# 10-RF_WIFI.net
KiCad netlist of a schematic drawn in Altium Designer
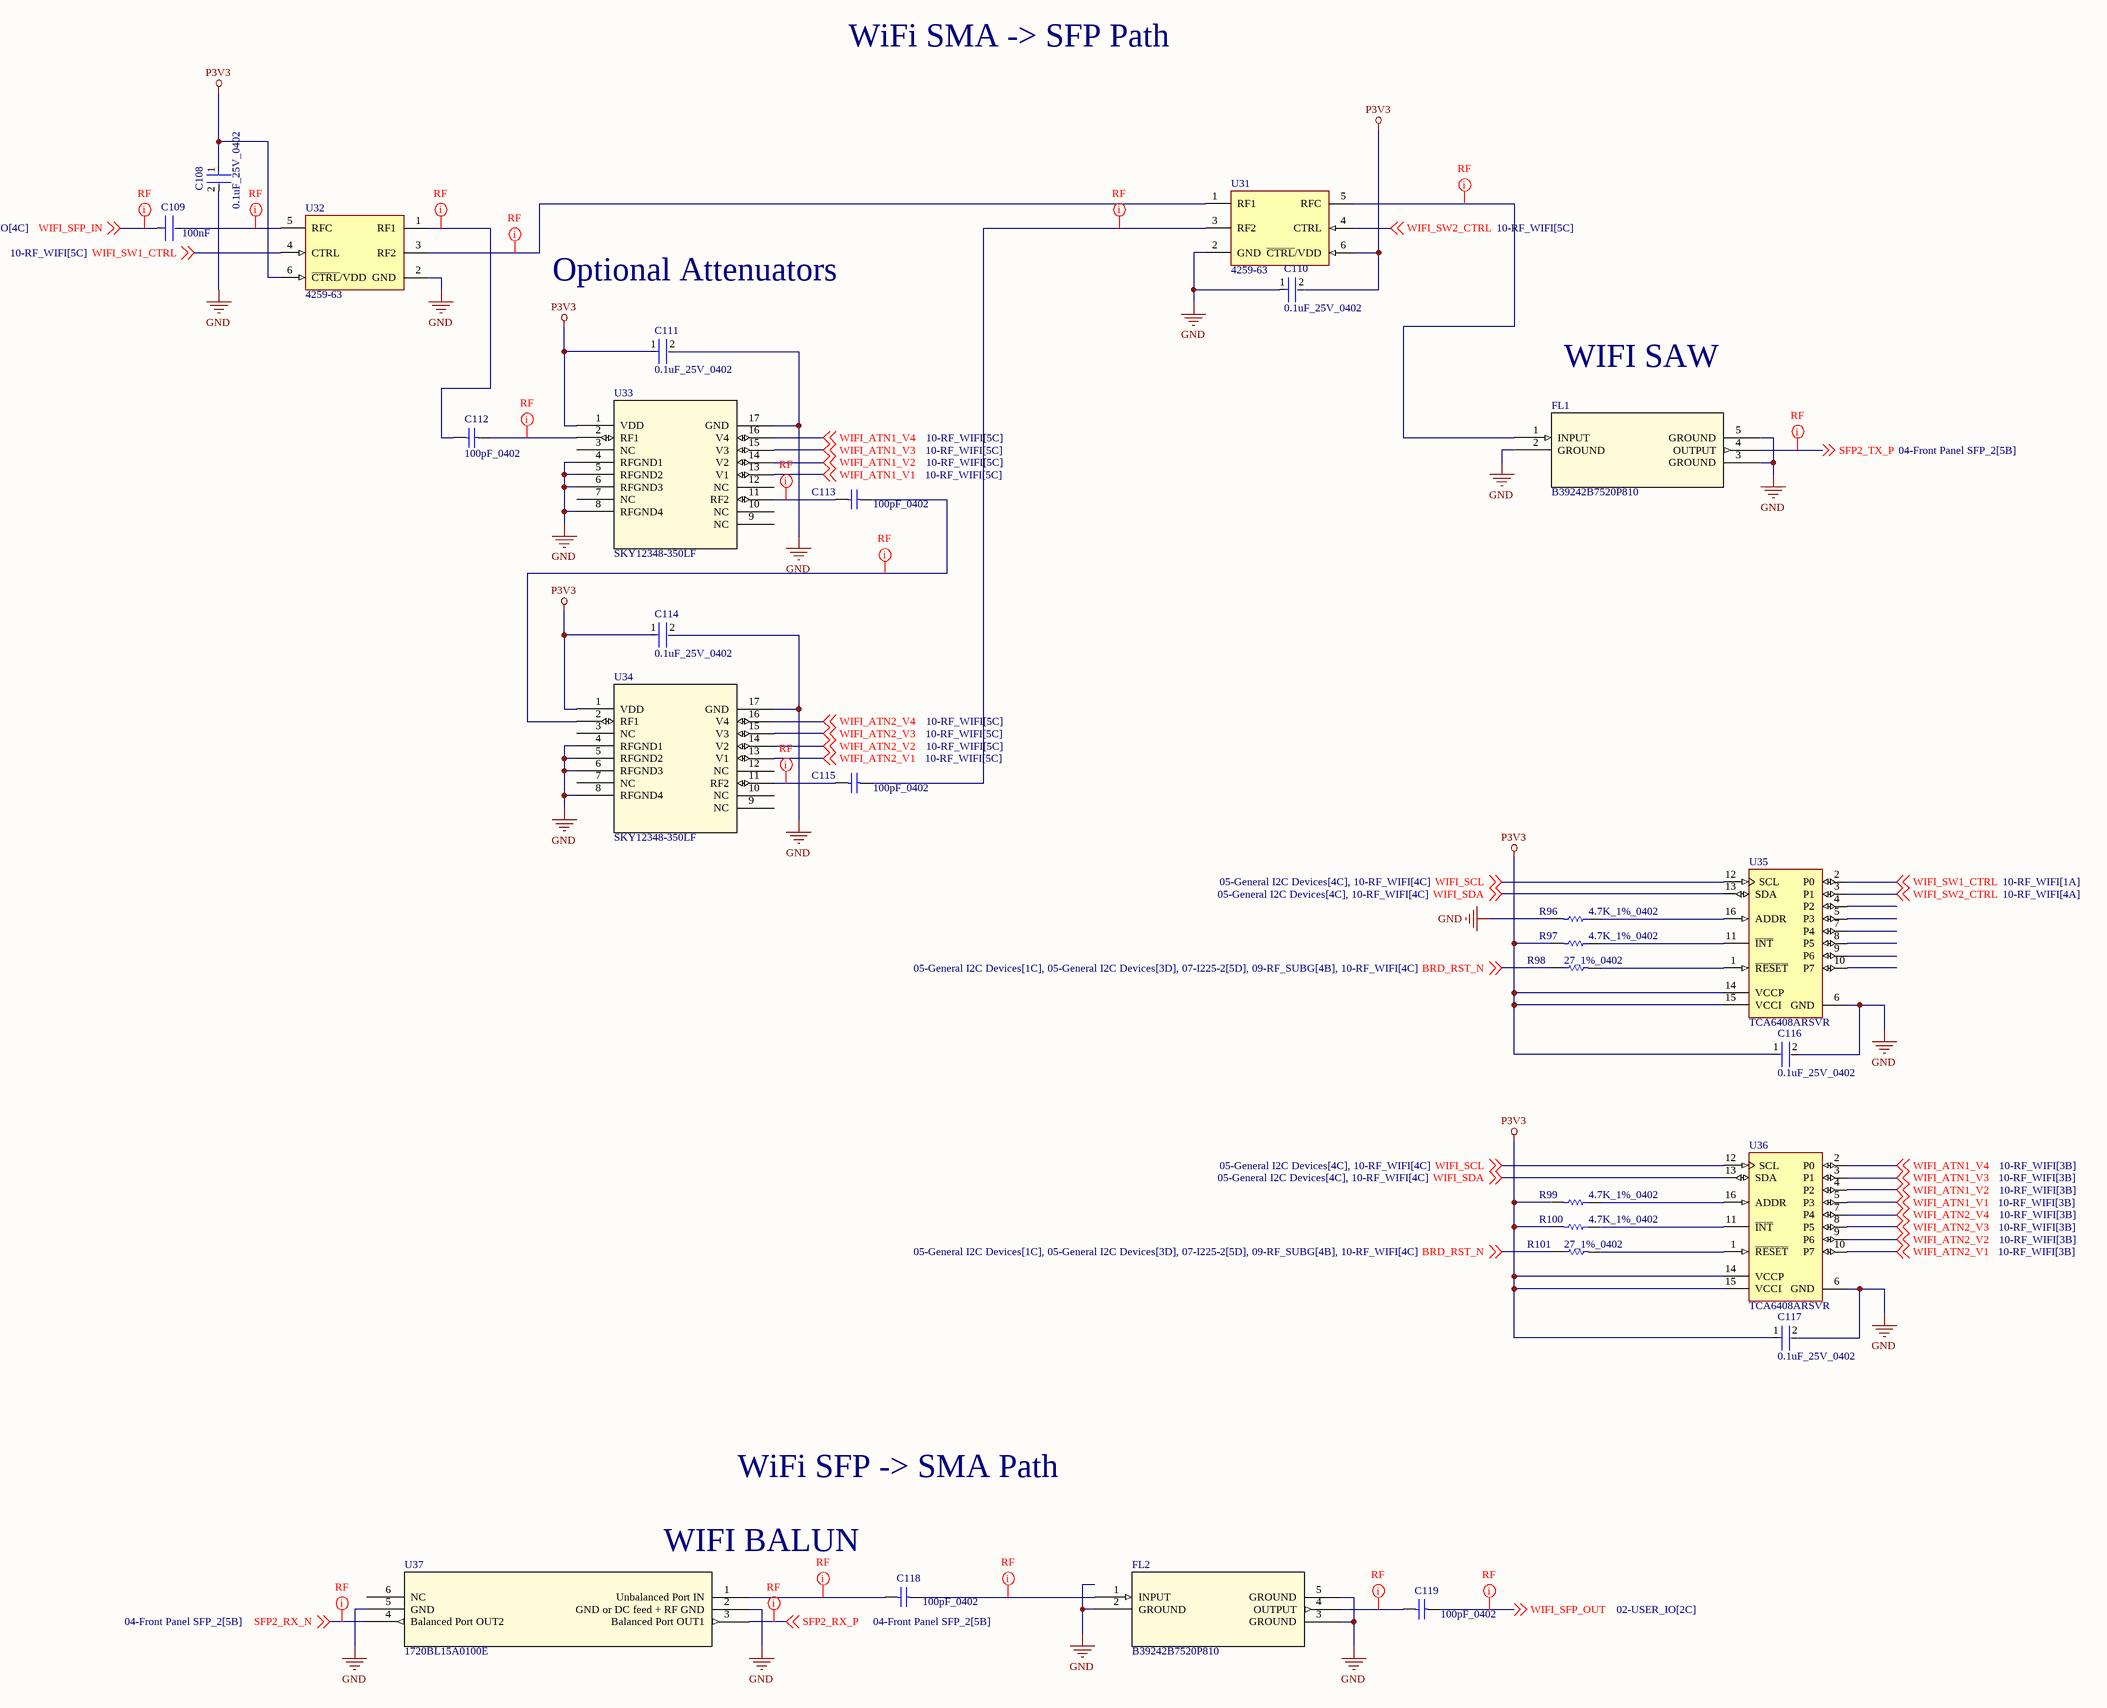
[diagram p0: 10-RF_WIFI.SchDoc]

(export (version "E")
  (design (tool "Eeschema 10.0.6"))
  (components
    (comp (ref "C108")
      (value "0.1uF_25V_0402")
      (footprint "FP-0402-L_1_0_1-W_0_5_0_1-IPC_C")
      (description "General Purpose Ceramic Capacitor, 0402, 100nF, 10%, X7R, 15%, 25V")
      (fields (field (name "VOLTAGE") "25V") (field (name "TOLERANCE") "10%"))
      (libsource (lib "Altium Content Vault") (part "b4654b650e69147ec39a6b967a45e02"))
    )
    (comp (ref "C109")
      (value "100nF")
      (footprint "FP-0402-L_1_0_0_05-W_0_5-IPC_B")
      (description "None")
      (fields (field (name "TOLERANCE") "10%"))
      (libsource (lib "") (part "b4654b650e69147ec39a6b967a45e02_1"))
    )
    (comp (ref "C110")
      (value "0.1uF_25V_0402")
      (footprint "FP-0402-L_1_0_1-W_0_5_0_1-IPC_C")
      (description "General Purpose Ceramic Capacitor, 0402, 100nF, 10%, X7R, 15%, 25V")
      (fields (field (name "VOLTAGE") "25V") (field (name "TOLERANCE") "10%"))
      (libsource (lib "Altium Content Vault") (part "b4654b650e69147ec39a6b967a45e02"))
    )
    (comp (ref "C111")
      (value "0.1uF_25V_0402")
      (footprint "FP-0402-L_1_0_1-W_0_5_0_1-IPC_C")
      (description "General Purpose Ceramic Capacitor, 0402, 100nF, 10%, X7R, 15%, 25V")
      (fields (field (name "VOLTAGE") "25V") (field (name "TOLERANCE") "10%"))
      (libsource (lib "Altium Content Vault") (part "b4654b650e69147ec39a6b967a45e02"))
    )
    (comp (ref "C112")
      (value "100pF_0402")
      (footprint "CAPC1005X55X25ML05T10")
      (fields (field (name "MANUFACTURER") "Murata") (field (name "PART NUMBER") "GRM1555C1H101JA01D"))
      (libsource (lib "Altium Content Vault") (part "CAP"))
    )
    (comp (ref "C113")
      (value "100pF_0402")
      (footprint "CAPC1005X55X25ML05T10")
      (fields (field (name "MANUFACTURER") "Murata") (field (name "PART NUMBER") "GRM1555C1H101JA01D"))
      (libsource (lib "Altium Content Vault") (part "CAP"))
    )
    (comp (ref "C114")
      (value "0.1uF_25V_0402")
      (footprint "FP-0402-L_1_0_1-W_0_5_0_1-IPC_C")
      (description "General Purpose Ceramic Capacitor, 0402, 100nF, 10%, X7R, 15%, 25V")
      (fields (field (name "VOLTAGE") "25V") (field (name "TOLERANCE") "10%"))
      (libsource (lib "Altium Content Vault") (part "b4654b650e69147ec39a6b967a45e02"))
    )
    (comp (ref "C115")
      (value "100pF_0402")
      (footprint "CAPC1005X55X25ML05T10")
      (fields (field (name "MANUFACTURER") "Murata") (field (name "PART NUMBER") "GRM1555C1H101JA01D"))
      (libsource (lib "Altium Content Vault") (part "CAP"))
    )
    (comp (ref "C116")
      (value "0.1uF_25V_0402")
      (footprint "FP-0402-L_1_0_1-W_0_5_0_1-IPC_C")
      (description "General Purpose Ceramic Capacitor, 0402, 100nF, 10%, X7R, 15%, 25V")
      (fields (field (name "VOLTAGE") "25V") (field (name "TOLERANCE") "10%"))
      (libsource (lib "Altium Content Vault") (part "b4654b650e69147ec39a6b967a45e02"))
    )
    (comp (ref "C117")
      (value "0.1uF_25V_0402")
      (footprint "FP-0402-L_1_0_1-W_0_5_0_1-IPC_C")
      (description "General Purpose Ceramic Capacitor, 0402, 100nF, 10%, X7R, 15%, 25V")
      (fields (field (name "VOLTAGE") "25V") (field (name "TOLERANCE") "10%"))
      (libsource (lib "Altium Content Vault") (part "b4654b650e69147ec39a6b967a45e02"))
    )
    (comp (ref "C118")
      (value "100pF_0402")
      (footprint "CAPC1005X55X25ML05T10")
      (fields (field (name "MANUFACTURER") "Murata") (field (name "PART NUMBER") "GRM1555C1H101JA01D"))
      (libsource (lib "Altium Content Vault") (part "CAP"))
    )
    (comp (ref "C119")
      (value "100pF_0402")
      (footprint "CAPC1005X55X25ML05T10")
      (fields (field (name "MANUFACTURER") "Murata") (field (name "PART NUMBER") "GRM1555C1H101JA01D"))
      (libsource (lib "Altium Content Vault") (part "CAP"))
    )
    (comp (ref "FL1")
      (value "B39242B7520P810")
      (footprint "SMD5_SAW-B7520_QUA")
      (description "No Description Available")
      (libsource (lib "B39242B7520P810") (part "B39242B7520P810"))
    )
    (comp (ref "FL2")
      (value "B39242B7520P810")
      (footprint "SMD5_SAW-B7520_QUA")
      (description "No Description Available")
      (libsource (lib "B39242B7520P810") (part "B39242B7520P810"))
    )
    (comp (ref "R96")
      (value "4.7K_1%_0402")
      (footprint "RESC1005X40X25NL10T10")
      (fields (field (name "MANUFACTURER") "Bourns") (field (name "PART NUMBER") "CR0402-FX-4701GLF"))
      (libsource (lib "Altium Content Vault") (part "RES"))
    )
    (comp (ref "R97")
      (value "4.7K_1%_0402")
      (footprint "RESC1005X40X25NL10T10")
      (fields (field (name "MANUFACTURER") "Bourns") (field (name "PART NUMBER") "CR0402-FX-4701GLF"))
      (libsource (lib "Altium Content Vault") (part "RES"))
    )
    (comp (ref "R98")
      (value "27_1%_0402")
      (footprint "RESC1005X40X25NL05T05")
      (fields (field (name "PART NUMBER") "CRCW040227R0FKED") (field (name "MANUFACTURER") "Vishay Dale"))
      (libsource (lib "Altium Content Vault") (part "RES"))
    )
    (comp (ref "R99")
      (value "4.7K_1%_0402")
      (footprint "RESC1005X40X25NL10T10")
      (fields (field (name "MANUFACTURER") "Bourns") (field (name "PART NUMBER") "CR0402-FX-4701GLF"))
      (libsource (lib "Altium Content Vault") (part "RES"))
    )
    (comp (ref "R100")
      (value "4.7K_1%_0402")
      (footprint "RESC1005X40X25NL10T10")
      (fields (field (name "MANUFACTURER") "Bourns") (field (name "PART NUMBER") "CR0402-FX-4701GLF"))
      (libsource (lib "Altium Content Vault") (part "RES"))
    )
    (comp (ref "R101")
      (value "27_1%_0402")
      (footprint "RESC1005X40X25NL05T05")
      (fields (field (name "PART NUMBER") "CRCW040227R0FKED") (field (name "MANUFACTURER") "Vishay Dale"))
      (libsource (lib "Altium Content Vault") (part "RES"))
    )
    (comp (ref "U31")
      (value "4259-63")
      (footprint "PERE-SC-70-6_M")
      (description "IC RF Switch SPDT, 50 Ohm, 6-Pin SC70, RoHS, Tape and Reel")
      (fields (field (name "MANUFACTURER") "Peregrine Semiconductor"))
      (libsource (lib "Altium Content Vault") (part "PERE-PE4259-6"))
    )
    (comp (ref "U32")
      (value "4259-63")
      (footprint "PERE-SC-70-6_M")
      (description "IC RF Switch SPDT, 50 Ohm, 6-Pin SC70, RoHS, Tape and Reel")
      (fields (field (name "MANUFACTURER") "Peregrine Semiconductor"))
      (libsource (lib "") (part "PERE-PE4259-6_1"))
    )
    (comp (ref "U33")
      (value "SKY12348-350LF")
      (footprint "SKY12348-350LF_SKY")
      (description "No Description Available")
      (libsource (lib "SKY12348-350LF") (part "SKY12348-350LF"))
    )
    (comp (ref "U34")
      (value "SKY12348-350LF")
      (footprint "SKY12348-350LF_SKY")
      (description "No Description Available")
      (libsource (lib "SKY12348-350LF") (part "SKY12348-350LF"))
    )
    (comp (ref "U35")
      (value "TCA6408ARSVR")
      (footprint "RSV0016A_V")
      (fields (field (name "MANUFACTURER") "Texas Instruments"))
      (libsource (lib "Altium Content Vault") (part "TI-TCA6408A-UQFN_RSV-16"))
    )
    (comp (ref "U36")
      (value "TCA6408ARSVR")
      (footprint "RSV0016A_V")
      (fields (field (name "MANUFACTURER") "Texas Instruments"))
      (libsource (lib "Altium Content Vault") (part "TI-TCA6408A-UQFN_RSV-16"))
    )
    (comp (ref "U37")
      (value "1720BL15A0100E")
      (footprint "SMT_15B0050E_JOT")
      (description "No Description Available")
      (libsource (lib "1720BL15A0100E") (part "1720BL15A0100E"))
    )
  )
  (nets
    (net (code "1") (name "BRD_RST_N") (class "Default")
      (node (ref "R101") (pin "1") (pinfunction "1_1") (pintype "passive"))
      (node (ref "R98") (pin "1") (pinfunction "1_1") (pintype "passive"))
    )
    (net (code "2") (name "GND") (class "Default")
      (node (ref "C108") (pin "2") (pinfunction "2_2") (pintype "passive"))
      (node (ref "C110") (pin "1") (pinfunction "1_1") (pintype "passive"))
      (node (ref "C111") (pin "2") (pinfunction "2_2") (pintype "passive"))
      (node (ref "C114") (pin "2") (pinfunction "2_2") (pintype "passive"))
      (node (ref "C116") (pin "2") (pinfunction "2_2") (pintype "passive"))
      (node (ref "C117") (pin "2") (pinfunction "2_2") (pintype "passive"))
      (node (ref "FL1") (pin "2") (pinfunction "GROUND_2") (pintype "power_in"))
      (node (ref "FL1") (pin "3") (pinfunction "GROUND_3") (pintype "power_in"))
      (node (ref "FL1") (pin "5") (pinfunction "GROUND_5") (pintype "power_in"))
      (node (ref "FL2") (pin "2") (pinfunction "GROUND_2") (pintype "power_in"))
      (node (ref "FL2") (pin "3") (pinfunction "GROUND_3") (pintype "power_in"))
      (node (ref "FL2") (pin "5") (pinfunction "GROUND_5") (pintype "power_in"))
      (node (ref "R96") (pin "2") (pinfunction "2_2") (pintype "passive"))
      (node (ref "U31") (pin "2") (pinfunction "GND_2") (pintype "power_in"))
      (node (ref "U32") (pin "2") (pinfunction "GND_2") (pintype "power_in"))
      (node (ref "U33") (pin "17") (pinfunction "GND_17") (pintype "power_in"))
      (node (ref "U33") (pin "4") (pinfunction "RFGND1_4") (pintype "power_in"))
      (node (ref "U33") (pin "5") (pinfunction "RFGND2_5") (pintype "power_in"))
      (node (ref "U33") (pin "6") (pinfunction "RFGND3_6") (pintype "power_in"))
      (node (ref "U33") (pin "8") (pinfunction "RFGND4_8") (pintype "power_in"))
      (node (ref "U34") (pin "17") (pinfunction "GND_17") (pintype "power_in"))
      (node (ref "U34") (pin "4") (pinfunction "RFGND1_4") (pintype "power_in"))
      (node (ref "U34") (pin "5") (pinfunction "RFGND2_5") (pintype "power_in"))
      (node (ref "U34") (pin "6") (pinfunction "RFGND3_6") (pintype "power_in"))
      (node (ref "U34") (pin "8") (pinfunction "RFGND4_8") (pintype "power_in"))
      (node (ref "U35") (pin "6") (pinfunction "GND_6") (pintype "power_in"))
      (node (ref "U36") (pin "6") (pinfunction "GND_6") (pintype "power_in"))
      (node (ref "U37") (pin "2") (pinfunction "GND_or_DC_feed_+_RF_GND_2") (pintype "power_in"))
      (node (ref "U37") (pin "5") (pinfunction "GND_5") (pintype "power_in"))
    )
    (net (code "3") (name "Net-(FL1-INPUT)") (class "Default")
      (node (ref "FL1") (pin "1") (pinfunction "INPUT_1") (pintype "input"))
      (node (ref "U31") (pin "5") (pinfunction "RFC_5") (pintype "passive"))
    )
    (net (code "4") (name "Net-(FL2-INPUT)") (class "Default")
      (node (ref "C118") (pin "2") (pinfunction "2_2") (pintype "passive"))
      (node (ref "FL2") (pin "1") (pinfunction "INPUT_1") (pintype "input"))
    )
    (net (code "5") (name "Net-(FL2-OUTPUT)") (class "Default")
      (node (ref "C119") (pin "1") (pinfunction "1_1") (pintype "passive"))
      (node (ref "FL2") (pin "4") (pinfunction "OUTPUT_4") (pintype "output"))
    )
    (net (code "6") (name "Net-(U31-RF1)") (class "Default")
      (node (ref "U31") (pin "1") (pinfunction "RF1_1") (pintype "passive"))
      (node (ref "U32") (pin "3") (pinfunction "RF2_3") (pintype "passive"))
    )
    (net (code "7") (name "Net-(U31-RF2)") (class "Default")
      (node (ref "C115") (pin "2") (pinfunction "2_2") (pintype "passive"))
      (node (ref "U31") (pin "3") (pinfunction "RF2_3") (pintype "passive"))
    )
    (net (code "8") (name "Net-(U32-RF1)") (class "Default")
      (node (ref "C112") (pin "1") (pinfunction "1_1") (pintype "passive"))
      (node (ref "U32") (pin "1") (pinfunction "RF1_1") (pintype "passive"))
    )
    (net (code "9") (name "Net-(U32-RFC)") (class "Default")
      (node (ref "C109") (pin "2") (pinfunction "2_2") (pintype "passive"))
      (node (ref "U32") (pin "5") (pinfunction "RFC_5") (pintype "passive"))
    )
    (net (code "10") (name "Net-(U33-RF1)") (class "Default")
      (node (ref "C112") (pin "2") (pinfunction "2_2") (pintype "passive"))
      (node (ref "U33") (pin "2") (pinfunction "RF1_2") (pintype "bidirectional"))
    )
    (net (code "11") (name "Net-(U33-RF2)") (class "Default")
      (node (ref "C113") (pin "1") (pinfunction "1_1") (pintype "passive"))
      (node (ref "U33") (pin "11") (pinfunction "RF2_11") (pintype "bidirectional"))
    )
    (net (code "12") (name "Net-(U34-RF1)") (class "Default")
      (node (ref "C113") (pin "2") (pinfunction "2_2") (pintype "passive"))
      (node (ref "U34") (pin "2") (pinfunction "RF1_2") (pintype "bidirectional"))
    )
    (net (code "13") (name "Net-(U34-RF2)") (class "Default")
      (node (ref "C115") (pin "1") (pinfunction "1_1") (pintype "passive"))
      (node (ref "U34") (pin "11") (pinfunction "RF2_11") (pintype "bidirectional"))
    )
    (net (code "14") (name "Net-(U35-ADDR)") (class "Default")
      (node (ref "R96") (pin "1") (pinfunction "1_1") (pintype "passive"))
      (node (ref "U35") (pin "16") (pinfunction "ADDR_16") (pintype "input"))
    )
    (net (code "15") (name "Net-(U35-~{INT})") (class "Default")
      (node (ref "R97") (pin "1") (pinfunction "1_1") (pintype "passive"))
      (node (ref "U35") (pin "11") (pinfunction "~{INT}_11") (pintype "open_collector"))
    )
    (net (code "16") (name "Net-(U35-~{RESET})") (class "Default")
      (node (ref "R98") (pin "2") (pinfunction "2_2") (pintype "passive"))
      (node (ref "U35") (pin "1") (pinfunction "~{RESET}_1") (pintype "input"))
    )
    (net (code "17") (name "Net-(U36-ADDR)") (class "Default")
      (node (ref "R99") (pin "1") (pinfunction "1_1") (pintype "passive"))
      (node (ref "U36") (pin "16") (pinfunction "ADDR_16") (pintype "input"))
    )
    (net (code "18") (name "Net-(U36-~{INT})") (class "Default")
      (node (ref "R100") (pin "1") (pinfunction "1_1") (pintype "passive"))
      (node (ref "U36") (pin "11") (pinfunction "~{INT}_11") (pintype "open_collector"))
    )
    (net (code "19") (name "Net-(U36-~{RESET})") (class "Default")
      (node (ref "R101") (pin "2") (pinfunction "2_2") (pintype "passive"))
      (node (ref "U36") (pin "1") (pinfunction "~{RESET}_1") (pintype "input"))
    )
    (net (code "20") (name "Net-(U37-Unbalanced_Port_IN)") (class "Default")
      (node (ref "C118") (pin "1") (pinfunction "1_1") (pintype "passive"))
      (node (ref "U37") (pin "1") (pinfunction "Unbalanced_Port_IN_1") (pintype "passive"))
    )
    (net (code "21") (name "P3V3") (class "Default")
      (node (ref "C108") (pin "1") (pinfunction "1_1") (pintype "passive"))
      (node (ref "C110") (pin "2") (pinfunction "2_2") (pintype "passive"))
      (node (ref "C111") (pin "1") (pinfunction "1_1") (pintype "passive"))
      (node (ref "C114") (pin "1") (pinfunction "1_1") (pintype "passive"))
      (node (ref "C116") (pin "1") (pinfunction "1_1") (pintype "passive"))
      (node (ref "C117") (pin "1") (pinfunction "1_1") (pintype "passive"))
      (node (ref "R100") (pin "2") (pinfunction "2_2") (pintype "passive"))
      (node (ref "R97") (pin "2") (pinfunction "2_2") (pintype "passive"))
      (node (ref "R99") (pin "2") (pinfunction "2_2") (pintype "passive"))
      (node (ref "U31") (pin "6") (pinfunction "~{CTRL}/VDD_6") (pintype "input"))
      (node (ref "U32") (pin "6") (pinfunction "~{CTRL}/VDD_6") (pintype "input"))
      (node (ref "U33") (pin "1") (pinfunction "VDD_1") (pintype "power_in"))
      (node (ref "U34") (pin "1") (pinfunction "VDD_1") (pintype "power_in"))
      (node (ref "U35") (pin "14") (pinfunction "VCCP_14") (pintype "power_in"))
      (node (ref "U35") (pin "15") (pinfunction "VCCI_15") (pintype "power_in"))
      (node (ref "U36") (pin "14") (pinfunction "VCCP_14") (pintype "power_in"))
      (node (ref "U36") (pin "15") (pinfunction "VCCI_15") (pintype "power_in"))
    )
    (net (code "22") (name "SFP2_RX_N") (class "Default")
      (node (ref "U37") (pin "4") (pinfunction "Balanced_Port_OUT2_4") (pintype "output"))
    )
    (net (code "23") (name "SFP2_RX_P") (class "Default")
      (node (ref "U37") (pin "3") (pinfunction "Balanced_Port_OUT1_3") (pintype "output"))
    )
    (net (code "24") (name "SFP2_TX_P") (class "Default")
      (node (ref "FL1") (pin "4") (pinfunction "OUTPUT_4") (pintype "output"))
    )
    (net (code "25") (name "WIFI_ATN1_V1") (class "Default")
      (node (ref "U33") (pin "13") (pinfunction "V1_13") (pintype "bidirectional"))
      (node (ref "U36") (pin "5") (pinfunction "P3_5") (pintype "bidirectional"))
    )
    (net (code "26") (name "WIFI_ATN1_V2") (class "Default")
      (node (ref "U33") (pin "14") (pinfunction "V2_14") (pintype "bidirectional"))
      (node (ref "U36") (pin "4") (pinfunction "P2_4") (pintype "bidirectional"))
    )
    (net (code "27") (name "WIFI_ATN1_V3") (class "Default")
      (node (ref "U33") (pin "15") (pinfunction "V3_15") (pintype "bidirectional"))
      (node (ref "U36") (pin "3") (pinfunction "P1_3") (pintype "bidirectional"))
    )
    (net (code "28") (name "WIFI_ATN1_V4") (class "Default")
      (node (ref "U33") (pin "16") (pinfunction "V4_16") (pintype "bidirectional"))
      (node (ref "U36") (pin "2") (pinfunction "P0_2") (pintype "bidirectional"))
    )
    (net (code "29") (name "WIFI_ATN2_V1") (class "Default")
      (node (ref "U34") (pin "13") (pinfunction "V1_13") (pintype "bidirectional"))
      (node (ref "U36") (pin "10") (pinfunction "P7_10") (pintype "bidirectional"))
    )
    (net (code "30") (name "WIFI_ATN2_V2") (class "Default")
      (node (ref "U34") (pin "14") (pinfunction "V2_14") (pintype "bidirectional"))
      (node (ref "U36") (pin "9") (pinfunction "P6_9") (pintype "bidirectional"))
    )
    (net (code "31") (name "WIFI_ATN2_V3") (class "Default")
      (node (ref "U34") (pin "15") (pinfunction "V3_15") (pintype "bidirectional"))
      (node (ref "U36") (pin "8") (pinfunction "P5_8") (pintype "bidirectional"))
    )
    (net (code "32") (name "WIFI_ATN2_V4") (class "Default")
      (node (ref "U34") (pin "16") (pinfunction "V4_16") (pintype "bidirectional"))
      (node (ref "U36") (pin "7") (pinfunction "P4_7") (pintype "bidirectional"))
    )
    (net (code "33") (name "WIFI_SCL") (class "Default")
      (node (ref "U35") (pin "12") (pinfunction "SCL_12") (pintype "input"))
      (node (ref "U36") (pin "12") (pinfunction "SCL_12") (pintype "input"))
    )
    (net (code "34") (name "WIFI_SDA") (class "Default")
      (node (ref "U35") (pin "13") (pinfunction "SDA_13") (pintype "bidirectional"))
      (node (ref "U36") (pin "13") (pinfunction "SDA_13") (pintype "bidirectional"))
    )
    (net (code "35") (name "WIFI_SFP_IN") (class "Default")
      (node (ref "C109") (pin "1") (pinfunction "1_1") (pintype "passive"))
    )
    (net (code "36") (name "WIFI_SFP_OUT") (class "Default")
      (node (ref "C119") (pin "2") (pinfunction "2_2") (pintype "passive"))
    )
    (net (code "37") (name "WIFI_SW1_CTRL") (class "Default")
      (node (ref "U32") (pin "4") (pinfunction "CTRL_4") (pintype "input"))
      (node (ref "U35") (pin "2") (pinfunction "P0_2") (pintype "bidirectional"))
    )
    (net (code "38") (name "WIFI_SW2_CTRL") (class "Default")
      (node (ref "U31") (pin "4") (pinfunction "CTRL_4") (pintype "input"))
      (node (ref "U35") (pin "3") (pinfunction "P1_3") (pintype "bidirectional"))
    )
    (net (code "39") (name "unconnected-(U33-NC-Pad3)") (class "Default")
      (node (ref "U33") (pin "3") (pinfunction "NC_3") (pintype "passive"))
    )
    (net (code "40") (name "unconnected-(U33-NC-Pad7)") (class "Default")
      (node (ref "U33") (pin "7") (pinfunction "NC_7") (pintype "passive"))
    )
    (net (code "41") (name "unconnected-(U33-NC-Pad9)") (class "Default")
      (node (ref "U33") (pin "9") (pinfunction "NC_9") (pintype "passive"))
    )
    (net (code "42") (name "unconnected-(U33-NC-Pad10)") (class "Default")
      (node (ref "U33") (pin "10") (pinfunction "NC_10") (pintype "passive"))
    )
    (net (code "43") (name "unconnected-(U33-NC-Pad12)") (class "Default")
      (node (ref "U33") (pin "12") (pinfunction "NC_12") (pintype "passive"))
    )
    (net (code "44") (name "unconnected-(U34-NC-Pad3)") (class "Default")
      (node (ref "U34") (pin "3") (pinfunction "NC_3") (pintype "passive"))
    )
    (net (code "45") (name "unconnected-(U34-NC-Pad7)") (class "Default")
      (node (ref "U34") (pin "7") (pinfunction "NC_7") (pintype "passive"))
    )
    (net (code "46") (name "unconnected-(U34-NC-Pad9)") (class "Default")
      (node (ref "U34") (pin "9") (pinfunction "NC_9") (pintype "passive"))
    )
    (net (code "47") (name "unconnected-(U34-NC-Pad10)") (class "Default")
      (node (ref "U34") (pin "10") (pinfunction "NC_10") (pintype "passive"))
    )
    (net (code "48") (name "unconnected-(U34-NC-Pad12)") (class "Default")
      (node (ref "U34") (pin "12") (pinfunction "NC_12") (pintype "passive"))
    )
    (net (code "49") (name "unconnected-(U35-P2-Pad4)") (class "Default")
      (node (ref "U35") (pin "4") (pinfunction "P2_4") (pintype "bidirectional"))
    )
    (net (code "50") (name "unconnected-(U35-P3-Pad5)") (class "Default")
      (node (ref "U35") (pin "5") (pinfunction "P3_5") (pintype "bidirectional"))
    )
    (net (code "51") (name "unconnected-(U35-P4-Pad7)") (class "Default")
      (node (ref "U35") (pin "7") (pinfunction "P4_7") (pintype "bidirectional"))
    )
    (net (code "52") (name "unconnected-(U35-P5-Pad8)") (class "Default")
      (node (ref "U35") (pin "8") (pinfunction "P5_8") (pintype "bidirectional"))
    )
    (net (code "53") (name "unconnected-(U35-P6-Pad9)") (class "Default")
      (node (ref "U35") (pin "9") (pinfunction "P6_9") (pintype "bidirectional"))
    )
    (net (code "54") (name "unconnected-(U35-P7-Pad10)") (class "Default")
      (node (ref "U35") (pin "10") (pinfunction "P7_10") (pintype "bidirectional"))
    )
    (net (code "55") (name "unconnected-(U37-NC-Pad6)") (class "Default")
      (node (ref "U37") (pin "6") (pinfunction "NC_6") (pintype "passive"))
    )
  )
)
